# vco.net
KiCad netlist of a schematic drawn in EAGLE
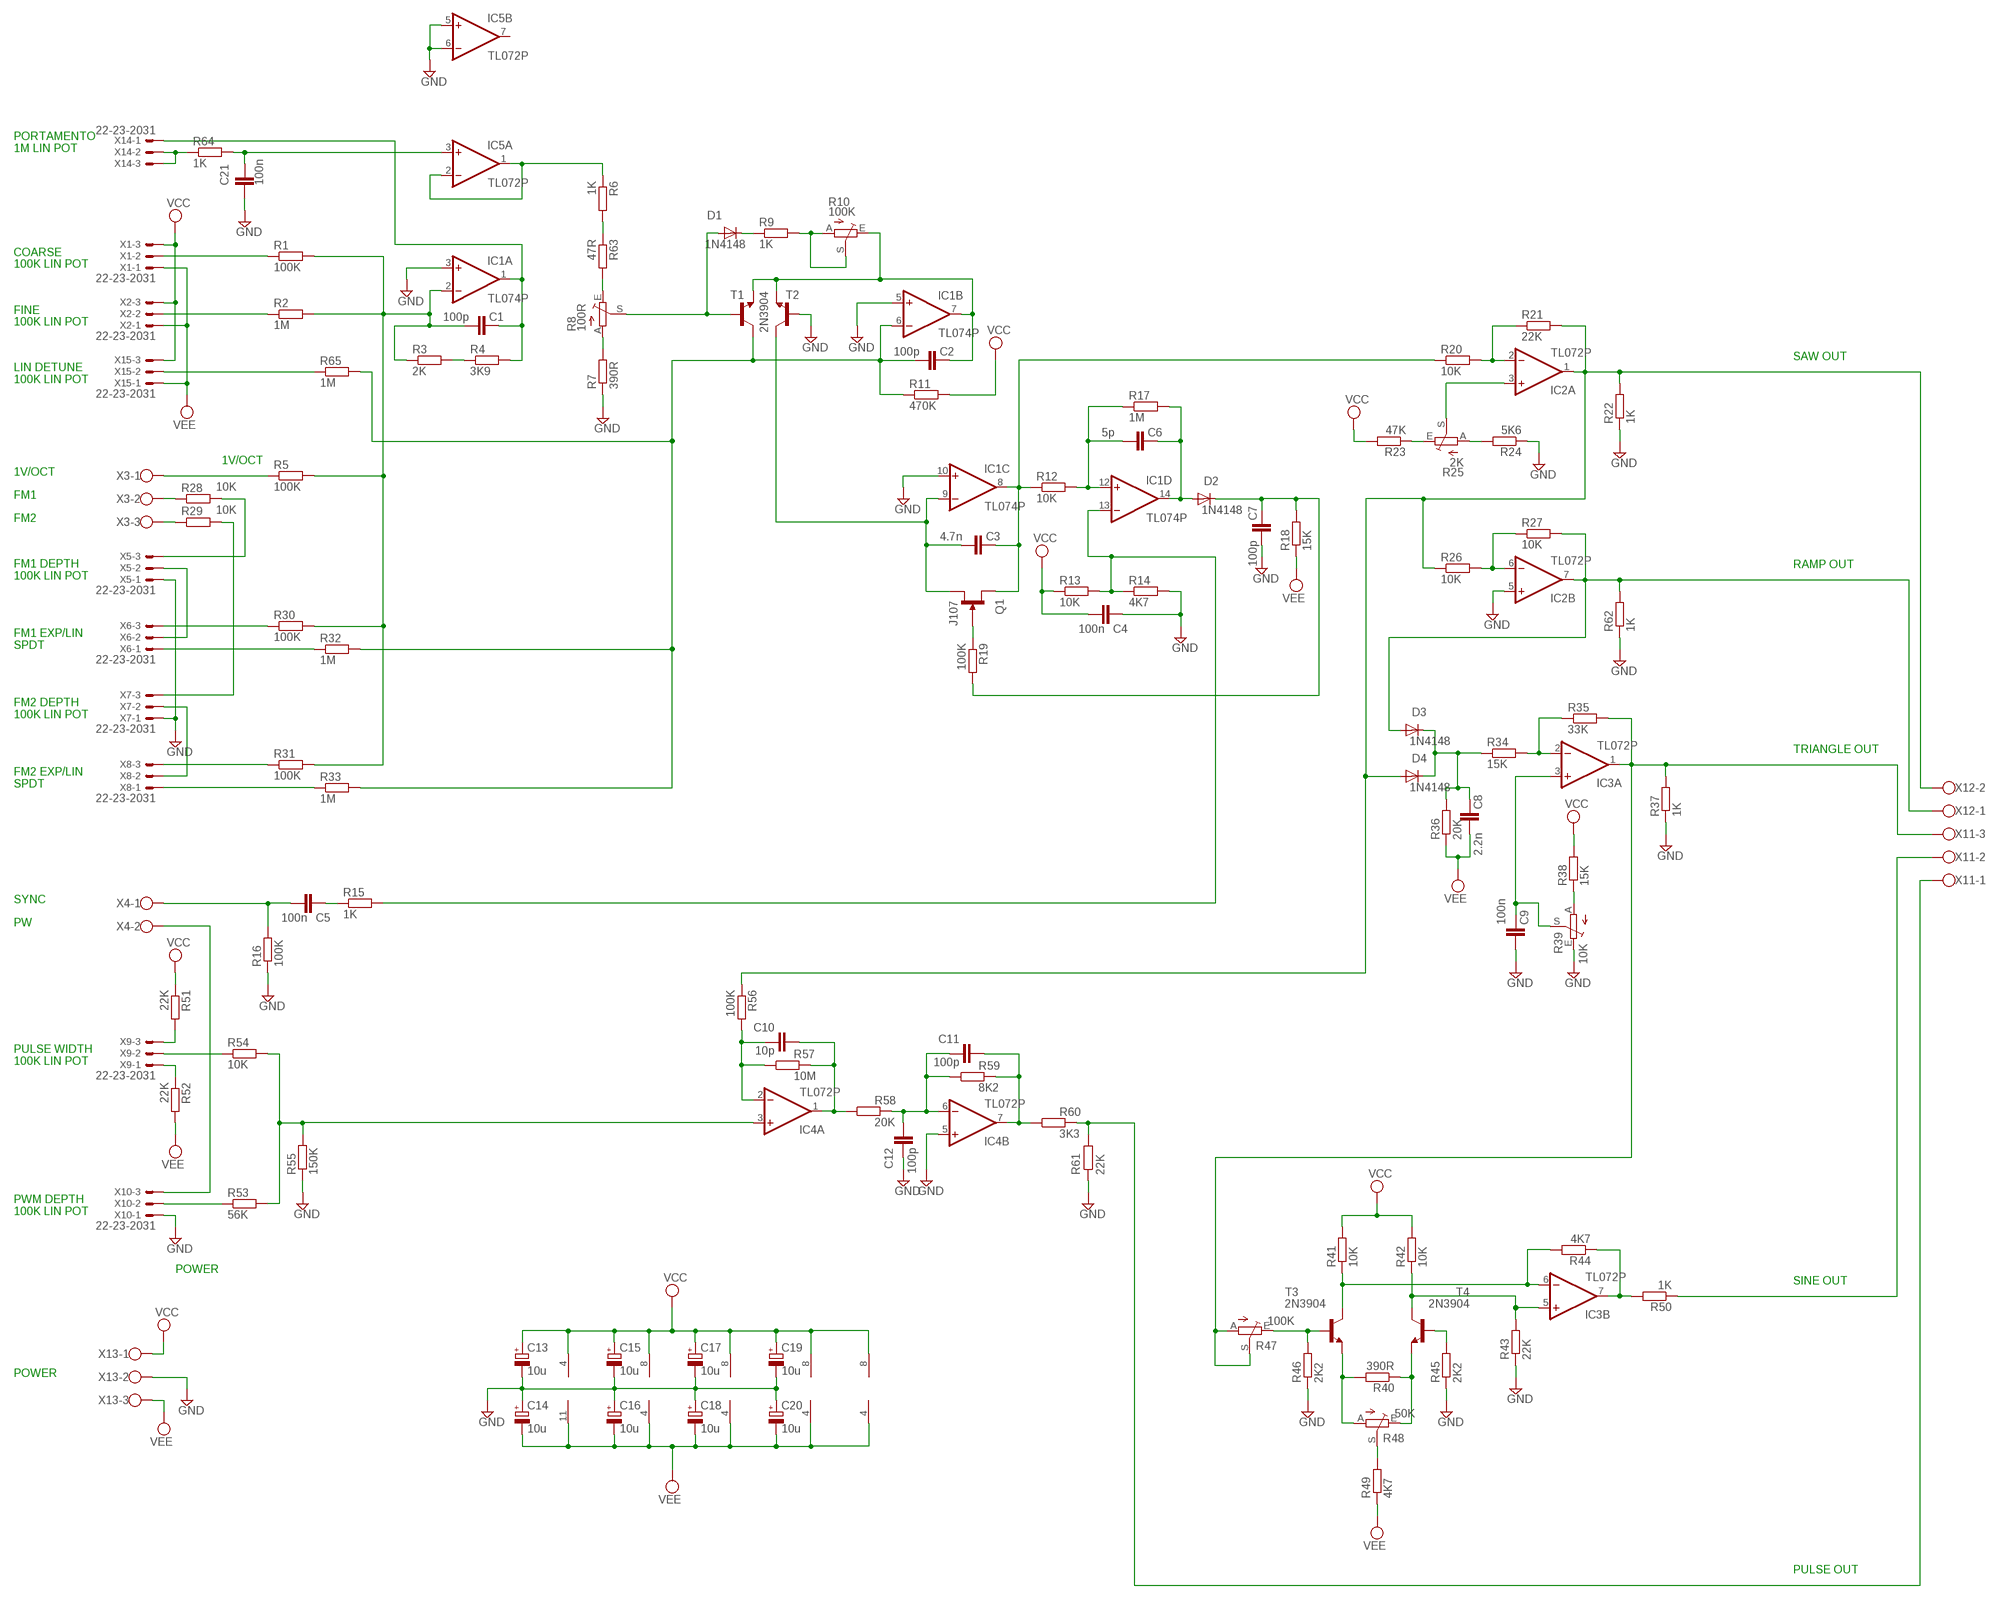
[diagram p0: schematic, sheet 1]

(export (version "E")
  (design (tool "Eeschema 10.0.6"))
  (components
    (comp (ref "C1")
      (value "100p")
      (footprint "eagle-import:C025-024X044")
      (libsource (lib "eagle-import") (part "C-EU025-024X044"))
    )
    (comp (ref "C2")
      (value "100p")
      (footprint "eagle-import:C025-024X044")
      (libsource (lib "eagle-import") (part "C-EU025-024X044"))
    )
    (comp (ref "C3")
      (value "4.7n")
      (footprint "eagle-import:C025-024X044")
      (libsource (lib "eagle-import") (part "C-EU025-024X044"))
    )
    (comp (ref "C4")
      (value "100n")
      (footprint "eagle-import:C025-024X044")
      (libsource (lib "eagle-import") (part "C-EU025-024X044"))
    )
    (comp (ref "C5")
      (value "100n")
      (footprint "eagle-import:C025-024X044")
      (libsource (lib "eagle-import") (part "C-EU025-024X044"))
    )
    (comp (ref "C6")
      (value "5p")
      (footprint "eagle-import:C025-024X044")
      (libsource (lib "eagle-import") (part "C-EU025-024X044"))
    )
    (comp (ref "C7")
      (value "100p")
      (footprint "eagle-import:C025-024X044")
      (libsource (lib "eagle-import") (part "C-EU025-024X044"))
    )
    (comp (ref "C8")
      (value "2.2n")
      (footprint "eagle-import:C025-024X044")
      (libsource (lib "eagle-import") (part "C-EU025-024X044"))
    )
    (comp (ref "C9")
      (value "100n")
      (footprint "eagle-import:C025-024X044")
      (libsource (lib "eagle-import") (part "C-EU025-024X044"))
    )
    (comp (ref "C10")
      (value "10p")
      (footprint "eagle-import:C025-024X044")
      (libsource (lib "eagle-import") (part "C-EU025-024X044"))
    )
    (comp (ref "C11")
      (value "100p")
      (footprint "eagle-import:C025-024X044")
      (libsource (lib "eagle-import") (part "C-EU025-024X044"))
    )
    (comp (ref "C12")
      (value "100p")
      (footprint "eagle-import:C025-024X044")
      (libsource (lib "eagle-import") (part "C-EU025-024X044"))
    )
    (comp (ref "C13")
      (value "10u")
      (footprint "eagle-import:E1,8-4")
      (libsource (lib "eagle-import") (part "CPOL-EUE1.8-4"))
    )
    (comp (ref "C14")
      (value "10u")
      (footprint "eagle-import:E1,8-4")
      (libsource (lib "eagle-import") (part "CPOL-EUE1.8-4"))
    )
    (comp (ref "C15")
      (value "10u")
      (footprint "eagle-import:E1,8-4")
      (libsource (lib "eagle-import") (part "CPOL-EUE1.8-4"))
    )
    (comp (ref "C16")
      (value "10u")
      (footprint "eagle-import:E1,8-4")
      (libsource (lib "eagle-import") (part "CPOL-EUE1.8-4"))
    )
    (comp (ref "C17")
      (value "10u")
      (footprint "eagle-import:E1,8-4")
      (libsource (lib "eagle-import") (part "CPOL-EUE1.8-4"))
    )
    (comp (ref "C18")
      (value "10u")
      (footprint "eagle-import:E1,8-4")
      (libsource (lib "eagle-import") (part "CPOL-EUE1.8-4"))
    )
    (comp (ref "C19")
      (value "10u")
      (footprint "eagle-import:E1,8-4")
      (libsource (lib "eagle-import") (part "CPOL-EUE1.8-4"))
    )
    (comp (ref "C20")
      (value "10u")
      (footprint "eagle-import:E1,8-4")
      (libsource (lib "eagle-import") (part "CPOL-EUE1.8-4"))
    )
    (comp (ref "C21")
      (value "100n")
      (footprint "eagle-import:C025-024X044")
      (libsource (lib "eagle-import") (part "C-EU025-024X044"))
    )
    (comp (ref "D1")
      (value "1N4148")
      (footprint "eagle-import:DO35-7")
      (libsource (lib "eagle-import") (part "1N4148DO35-7"))
    )
    (comp (ref "D2")
      (value "1N4148")
      (footprint "eagle-import:DO35-7")
      (libsource (lib "eagle-import") (part "1N4148DO35-7"))
    )
    (comp (ref "D3")
      (value "1N4148")
      (footprint "eagle-import:DO35-7")
      (libsource (lib "eagle-import") (part "1N4148DO35-7"))
    )
    (comp (ref "D4")
      (value "1N4148")
      (footprint "eagle-import:DO35-7")
      (libsource (lib "eagle-import") (part "1N4148DO35-7"))
    )
    (comp (ref "IC1")
      (value "TL074P")
      (footprint "eagle-import:DIL14")
      (libsource (lib "eagle-import") (part "TL074P"))
    )
    (comp (ref "IC2")
      (value "TL072P")
      (footprint "eagle-import:DIL08")
      (libsource (lib "eagle-import") (part "TL072P"))
    )
    (comp (ref "IC3")
      (value "TL072P")
      (footprint "eagle-import:DIL08")
      (libsource (lib "eagle-import") (part "TL072P"))
    )
    (comp (ref "IC4")
      (value "TL072P")
      (footprint "eagle-import:DIL08")
      (libsource (lib "eagle-import") (part "TL072P"))
    )
    (comp (ref "IC5")
      (value "TL072P")
      (footprint "eagle-import:DIL08")
      (libsource (lib "eagle-import") (part "TL072P"))
    )
    (comp (ref "Q1")
      (value "J107")
      (footprint "eagle-import:TO92R")
      (libsource (lib "eagle-import") (part "J105"))
    )
    (comp (ref "R1")
      (value "100K")
      (footprint "eagle-import:0204_7")
      (libsource (lib "eagle-import") (part "R-EU_0204/7"))
    )
    (comp (ref "R2")
      (value "1M")
      (footprint "eagle-import:0204_7")
      (libsource (lib "eagle-import") (part "R-EU_0204/7"))
    )
    (comp (ref "R3")
      (value "2K")
      (footprint "eagle-import:0309_12")
      (libsource (lib "eagle-import") (part "R-EU_0309/12"))
    )
    (comp (ref "R4")
      (value "3K9")
      (footprint "eagle-import:0204_7")
      (libsource (lib "eagle-import") (part "R-EU_0204/7"))
    )
    (comp (ref "R5")
      (value "100K")
      (footprint "eagle-import:0204_7")
      (libsource (lib "eagle-import") (part "R-EU_0204/7"))
    )
    (comp (ref "R6")
      (value "1K")
      (footprint "eagle-import:0204_7")
      (libsource (lib "eagle-import") (part "R-EU_0204/7"))
    )
    (comp (ref "R7")
      (value "390R")
      (footprint "eagle-import:0204_7")
      (libsource (lib "eagle-import") (part "R-EU_0204/7"))
    )
    (comp (ref "R8")
      (value "100R")
      (footprint "eagle-import:B64Y")
      (libsource (lib "eagle-import") (part "TRIM_EU-B64Y"))
    )
    (comp (ref "R9")
      (value "1K")
      (footprint "eagle-import:0204_7")
      (libsource (lib "eagle-import") (part "R-EU_0204/7"))
    )
    (comp (ref "R10")
      (value "100K")
      (footprint "eagle-import:B64Y")
      (libsource (lib "eagle-import") (part "TRIM_EU-B64Y"))
    )
    (comp (ref "R11")
      (value "470K")
      (footprint "eagle-import:0204_7")
      (libsource (lib "eagle-import") (part "R-EU_0204/7"))
    )
    (comp (ref "R12")
      (value "10K")
      (footprint "eagle-import:0204_7")
      (libsource (lib "eagle-import") (part "R-EU_0204/7"))
    )
    (comp (ref "R13")
      (value "10K")
      (footprint "eagle-import:0204_7")
      (libsource (lib "eagle-import") (part "R-EU_0204/7"))
    )
    (comp (ref "R14")
      (value "4K7")
      (footprint "eagle-import:0204_7")
      (libsource (lib "eagle-import") (part "R-EU_0204/7"))
    )
    (comp (ref "R15")
      (value "1K")
      (footprint "eagle-import:0204_7")
      (libsource (lib "eagle-import") (part "R-EU_0204/7"))
    )
    (comp (ref "R16")
      (value "100K")
      (footprint "eagle-import:0204_7")
      (libsource (lib "eagle-import") (part "R-EU_0204/7"))
    )
    (comp (ref "R17")
      (value "1M")
      (footprint "eagle-import:0204_7")
      (libsource (lib "eagle-import") (part "R-EU_0204/7"))
    )
    (comp (ref "R18")
      (value "15K")
      (footprint "eagle-import:0204_7")
      (libsource (lib "eagle-import") (part "R-EU_0204/7"))
    )
    (comp (ref "R19")
      (value "100K")
      (footprint "eagle-import:0204_7")
      (libsource (lib "eagle-import") (part "R-EU_0204/7"))
    )
    (comp (ref "R20")
      (value "10K")
      (footprint "eagle-import:0204_7")
      (libsource (lib "eagle-import") (part "R-EU_0204/7"))
    )
    (comp (ref "R21")
      (value "22K")
      (footprint "eagle-import:0204_7")
      (libsource (lib "eagle-import") (part "R-EU_0204/7"))
    )
    (comp (ref "R22")
      (value "1K")
      (footprint "eagle-import:0204_7")
      (libsource (lib "eagle-import") (part "R-EU_0204/7"))
    )
    (comp (ref "R23")
      (value "47K")
      (footprint "eagle-import:0204_7")
      (libsource (lib "eagle-import") (part "R-EU_0204/7"))
    )
    (comp (ref "R24")
      (value "5K6")
      (footprint "eagle-import:0204_7")
      (libsource (lib "eagle-import") (part "R-EU_0204/7"))
    )
    (comp (ref "R25")
      (value "2K")
      (footprint "eagle-import:B64Y")
      (libsource (lib "eagle-import") (part "TRIM_EU-B64Y"))
    )
    (comp (ref "R26")
      (value "10K")
      (footprint "eagle-import:0204_7")
      (libsource (lib "eagle-import") (part "R-EU_0204/7"))
    )
    (comp (ref "R27")
      (value "10K")
      (footprint "eagle-import:0204_7")
      (libsource (lib "eagle-import") (part "R-EU_0204/7"))
    )
    (comp (ref "R28")
      (value "10K")
      (footprint "eagle-import:0204_7")
      (libsource (lib "eagle-import") (part "R-EU_0204/7"))
    )
    (comp (ref "R29")
      (value "10K")
      (footprint "eagle-import:0204_7")
      (libsource (lib "eagle-import") (part "R-EU_0204/7"))
    )
    (comp (ref "R30")
      (value "100K")
      (footprint "eagle-import:0204_7")
      (libsource (lib "eagle-import") (part "R-EU_0204/7"))
    )
    (comp (ref "R31")
      (value "100K")
      (footprint "eagle-import:0204_7")
      (libsource (lib "eagle-import") (part "R-EU_0204/7"))
    )
    (comp (ref "R32")
      (value "1M")
      (footprint "eagle-import:0204_7")
      (libsource (lib "eagle-import") (part "R-EU_0204/7"))
    )
    (comp (ref "R33")
      (value "1M")
      (footprint "eagle-import:0204_7")
      (libsource (lib "eagle-import") (part "R-EU_0204/7"))
    )
    (comp (ref "R34")
      (value "15K")
      (footprint "eagle-import:0204_7")
      (libsource (lib "eagle-import") (part "R-EU_0204/7"))
    )
    (comp (ref "R35")
      (value "33K")
      (footprint "eagle-import:0204_7")
      (libsource (lib "eagle-import") (part "R-EU_0204/7"))
    )
    (comp (ref "R36")
      (value "20K")
      (footprint "eagle-import:0204_7")
      (libsource (lib "eagle-import") (part "R-EU_0204/7"))
    )
    (comp (ref "R37")
      (value "1K")
      (footprint "eagle-import:0204_7")
      (libsource (lib "eagle-import") (part "R-EU_0204/7"))
    )
    (comp (ref "R38")
      (value "15K")
      (footprint "eagle-import:0204_7")
      (libsource (lib "eagle-import") (part "R-EU_0204/7"))
    )
    (comp (ref "R39")
      (value "10K")
      (footprint "eagle-import:CA6V")
      (libsource (lib "eagle-import") (part "TRIM_EU-CA6V"))
    )
    (comp (ref "R40")
      (value "390R")
      (footprint "eagle-import:0204_7")
      (libsource (lib "eagle-import") (part "R-EU_0204/7"))
    )
    (comp (ref "R41")
      (value "10K")
      (footprint "eagle-import:0204_7")
      (libsource (lib "eagle-import") (part "R-EU_0204/7"))
    )
    (comp (ref "R42")
      (value "10K")
      (footprint "eagle-import:0204_7")
      (libsource (lib "eagle-import") (part "R-EU_0204/7"))
    )
    (comp (ref "R43")
      (value "22K")
      (footprint "eagle-import:0204_7")
      (libsource (lib "eagle-import") (part "R-EU_0204/7"))
    )
    (comp (ref "R44")
      (value "4K7")
      (footprint "eagle-import:0204_7")
      (libsource (lib "eagle-import") (part "R-EU_0204/7"))
    )
    (comp (ref "R45")
      (value "2K2")
      (footprint "eagle-import:0204_7")
      (libsource (lib "eagle-import") (part "R-EU_0204/7"))
    )
    (comp (ref "R46")
      (value "2K2")
      (footprint "eagle-import:0204_7")
      (libsource (lib "eagle-import") (part "R-EU_0204/7"))
    )
    (comp (ref "R47")
      (value "100K")
      (footprint "eagle-import:CA6V")
      (libsource (lib "eagle-import") (part "TRIM_EU-CA6V"))
    )
    (comp (ref "R48")
      (value "50K")
      (footprint "eagle-import:CA6V")
      (libsource (lib "eagle-import") (part "TRIM_EU-CA6V"))
    )
    (comp (ref "R49")
      (value "4K7")
      (footprint "eagle-import:0204_7")
      (libsource (lib "eagle-import") (part "R-EU_0204/7"))
    )
    (comp (ref "R50")
      (value "1K")
      (footprint "eagle-import:0204_7")
      (libsource (lib "eagle-import") (part "R-EU_0204/7"))
    )
    (comp (ref "R51")
      (value "22K")
      (footprint "eagle-import:0204_7")
      (libsource (lib "eagle-import") (part "R-EU_0204/7"))
    )
    (comp (ref "R52")
      (value "22K")
      (footprint "eagle-import:0204_7")
      (libsource (lib "eagle-import") (part "R-EU_0204/7"))
    )
    (comp (ref "R53")
      (value "56K")
      (footprint "eagle-import:0204_7")
      (libsource (lib "eagle-import") (part "R-EU_0204/7"))
    )
    (comp (ref "R54")
      (value "10K")
      (footprint "eagle-import:0204_7")
      (libsource (lib "eagle-import") (part "R-EU_0204/7"))
    )
    (comp (ref "R55")
      (value "150K")
      (footprint "eagle-import:0204_7")
      (libsource (lib "eagle-import") (part "R-EU_0204/7"))
    )
    (comp (ref "R56")
      (value "100K")
      (footprint "eagle-import:0204_7")
      (libsource (lib "eagle-import") (part "R-EU_0204/7"))
    )
    (comp (ref "R57")
      (value "10M")
      (footprint "eagle-import:0204_7")
      (libsource (lib "eagle-import") (part "R-EU_0204/7"))
    )
    (comp (ref "R58")
      (value "20K")
      (footprint "eagle-import:0204_7")
      (libsource (lib "eagle-import") (part "R-EU_0204/7"))
    )
    (comp (ref "R59")
      (value "8K2")
      (footprint "eagle-import:0204_7")
      (libsource (lib "eagle-import") (part "R-EU_0204/7"))
    )
    (comp (ref "R60")
      (value "3K3")
      (footprint "eagle-import:0204_7")
      (libsource (lib "eagle-import") (part "R-EU_0204/7"))
    )
    (comp (ref "R61")
      (value "22K")
      (footprint "eagle-import:0204_7")
      (libsource (lib "eagle-import") (part "R-EU_0204/7"))
    )
    (comp (ref "R62")
      (value "1K")
      (footprint "eagle-import:0204_7")
      (libsource (lib "eagle-import") (part "R-EU_0204/7"))
    )
    (comp (ref "R63")
      (value "47R")
      (footprint "eagle-import:0204_7")
      (libsource (lib "eagle-import") (part "R-EU_0204/7"))
    )
    (comp (ref "R64")
      (value "1K")
      (footprint "eagle-import:0204_7")
      (libsource (lib "eagle-import") (part "R-EU_0204/7"))
    )
    (comp (ref "R65")
      (value "1M")
      (footprint "eagle-import:0204_7")
      (libsource (lib "eagle-import") (part "R-EU_0204/7"))
    )
    (comp (ref "T1")
      (value "2N3904")
      (footprint "eagle-import:TO92")
      (libsource (lib "eagle-import") (part "2N3904"))
    )
    (comp (ref "T2")
      (value "2N3904")
      (footprint "eagle-import:TO92")
      (libsource (lib "eagle-import") (part "2N3904"))
    )
    (comp (ref "T3")
      (value "2N3904")
      (footprint "eagle-import:TO92")
      (libsource (lib "eagle-import") (part "2N3904"))
    )
    (comp (ref "T4")
      (value "2N3904")
      (footprint "eagle-import:TO92")
      (libsource (lib "eagle-import") (part "2N3904"))
    )
    (comp (ref "X1")
      (value "22-23-2031")
      (footprint "eagle-import:22-23-2031")
      (fields (field (name "MF") "MOLEX"))
      (libsource (lib "eagle-import") (part "22-23-2031"))
    )
    (comp (ref "X2")
      (value "22-23-2031")
      (footprint "eagle-import:22-23-2031")
      (fields (field (name "MF") "MOLEX"))
      (libsource (lib "eagle-import") (part "22-23-2031"))
    )
    (comp (ref "X3")
      (value "W237-103")
      (footprint "eagle-import:W237-103")
      (fields (field (name "MPN") "237-103"))
      (libsource (lib "eagle-import") (part "W237-103"))
    )
    (comp (ref "X4")
      (value "W237-102")
      (footprint "eagle-import:W237-102")
      (fields (field (name "MPN") "237-102"))
      (libsource (lib "eagle-import") (part "W237-102"))
    )
    (comp (ref "X5")
      (value "22-23-2031")
      (footprint "eagle-import:22-23-2031")
      (fields (field (name "MF") "MOLEX"))
      (libsource (lib "eagle-import") (part "22-23-2031"))
    )
    (comp (ref "X6")
      (value "22-23-2031")
      (footprint "eagle-import:22-23-2031")
      (fields (field (name "MF") "MOLEX"))
      (libsource (lib "eagle-import") (part "22-23-2031"))
    )
    (comp (ref "X7")
      (value "22-23-2031")
      (footprint "eagle-import:22-23-2031")
      (fields (field (name "MF") "MOLEX"))
      (libsource (lib "eagle-import") (part "22-23-2031"))
    )
    (comp (ref "X8")
      (value "22-23-2031")
      (footprint "eagle-import:22-23-2031")
      (fields (field (name "MF") "MOLEX"))
      (libsource (lib "eagle-import") (part "22-23-2031"))
    )
    (comp (ref "X9")
      (value "22-23-2031")
      (footprint "eagle-import:22-23-2031")
      (fields (field (name "MF") "MOLEX"))
      (libsource (lib "eagle-import") (part "22-23-2031"))
    )
    (comp (ref "X10")
      (value "22-23-2031")
      (footprint "eagle-import:22-23-2031")
      (fields (field (name "MF") "MOLEX"))
      (libsource (lib "eagle-import") (part "22-23-2031"))
    )
    (comp (ref "X11")
      (value "W237-103")
      (footprint "eagle-import:W237-103")
      (fields (field (name "MPN") "237-103"))
      (libsource (lib "eagle-import") (part "W237-103"))
    )
    (comp (ref "X12")
      (value "W237-102")
      (footprint "eagle-import:W237-102")
      (fields (field (name "MPN") "237-102"))
      (libsource (lib "eagle-import") (part "W237-102"))
    )
    (comp (ref "X13")
      (value "W237-103")
      (footprint "eagle-import:W237-103")
      (fields (field (name "MPN") "237-103"))
      (libsource (lib "eagle-import") (part "W237-103"))
    )
    (comp (ref "X14")
      (value "22-23-2031")
      (footprint "eagle-import:22-23-2031")
      (fields (field (name "MF") "MOLEX"))
      (libsource (lib "eagle-import") (part "22-23-2031"))
    )
    (comp (ref "X15")
      (value "22-23-2031")
      (footprint "eagle-import:22-23-2031")
      (fields (field (name "MF") "MOLEX"))
      (libsource (lib "eagle-import") (part "22-23-2031"))
    )
  )
  (nets
    (net (code "1") (name "GND") (class "Default")
      (node (ref "C12") (pin "1") (pinfunction "1_1") (pintype "passive"))
      (node (ref "C13") (pin "-") (pinfunction "-_-") (pintype "passive"))
      (node (ref "C14") (pin "+") (pinfunction "+_+") (pintype "passive"))
      (node (ref "C15") (pin "-") (pinfunction "-_-") (pintype "passive"))
      (node (ref "C16") (pin "+") (pinfunction "+_+") (pintype "passive"))
      (node (ref "C17") (pin "-") (pinfunction "-_-") (pintype "passive"))
      (node (ref "C18") (pin "+") (pinfunction "+_+") (pintype "passive"))
      (node (ref "C19") (pin "-") (pinfunction "-_-") (pintype "passive"))
      (node (ref "C20") (pin "+") (pinfunction "+_+") (pintype "passive"))
      (node (ref "C21") (pin "2") (pinfunction "2_2") (pintype "passive"))
      (node (ref "C4") (pin "1") (pinfunction "1_1") (pintype "passive"))
      (node (ref "C7") (pin "2") (pinfunction "2_2") (pintype "passive"))
      (node (ref "C9") (pin "2") (pinfunction "2_2") (pintype "passive"))
      (node (ref "IC1") (pin "10") (pinfunction "+IN_10") (pintype "input"))
      (node (ref "IC1") (pin "3") (pinfunction "+IN_3") (pintype "input"))
      (node (ref "IC1") (pin "5") (pinfunction "+IN_5") (pintype "input"))
      (node (ref "IC2") (pin "5") (pinfunction "+IN_5") (pintype "input"))
      (node (ref "IC4") (pin "5") (pinfunction "+IN_5") (pintype "input"))
      (node (ref "IC5") (pin "5") (pinfunction "+IN_5") (pintype "input"))
      (node (ref "IC5") (pin "6") (pinfunction "-IN_6") (pintype "input"))
      (node (ref "R14") (pin "2") (pinfunction "2_2") (pintype "passive"))
      (node (ref "R16") (pin "1") (pinfunction "1_1") (pintype "passive"))
      (node (ref "R22") (pin "1") (pinfunction "1_1") (pintype "passive"))
      (node (ref "R24") (pin "1") (pinfunction "1_1") (pintype "passive"))
      (node (ref "R37") (pin "1") (pinfunction "1_1") (pintype "passive"))
      (node (ref "R39") (pin "E") (pinfunction "E_E") (pintype "passive"))
      (node (ref "R43") (pin "1") (pinfunction "1_1") (pintype "passive"))
      (node (ref "R45") (pin "1") (pinfunction "1_1") (pintype "passive"))
      (node (ref "R46") (pin "1") (pinfunction "1_1") (pintype "passive"))
      (node (ref "R55") (pin "1") (pinfunction "1_1") (pintype "passive"))
      (node (ref "R61") (pin "1") (pinfunction "1_1") (pintype "passive"))
      (node (ref "R62") (pin "1") (pinfunction "1_1") (pintype "passive"))
      (node (ref "R7") (pin "1") (pinfunction "1_1") (pintype "passive"))
      (node (ref "T2") (pin "2") (pinfunction "B_2") (pintype "passive"))
      (node (ref "X10") (pin "1") (pinfunction "S_1") (pintype "passive"))
      (node (ref "X13") (pin "2") (pinfunction "KL_2") (pintype "passive"))
      (node (ref "X5") (pin "1") (pinfunction "S_1") (pintype "passive"))
      (node (ref "X7") (pin "1") (pinfunction "S_1") (pintype "passive"))
    )
    (net (code "2") (name "Net-(C5-Pad1)") (class "Default")
      (node (ref "C5") (pin "1") (pinfunction "1_1") (pintype "passive"))
      (node (ref "R15") (pin "1") (pinfunction "1_1") (pintype "passive"))
    )
    (net (code "3") (name "Net-(C7-Pad1)") (class "Default")
      (node (ref "C7") (pin "1") (pinfunction "1_1") (pintype "passive"))
      (node (ref "D2") (pin "C") (pinfunction "C_C") (pintype "passive"))
      (node (ref "R18") (pin "2") (pinfunction "2_2") (pintype "passive"))
      (node (ref "R19") (pin "2") (pinfunction "2_2") (pintype "passive"))
    )
    (net (code "4") (name "Net-(C8-Pad1)") (class "Default")
      (node (ref "C8") (pin "1") (pinfunction "1_1") (pintype "passive"))
      (node (ref "D3") (pin "C") (pinfunction "C_C") (pintype "passive"))
      (node (ref "D4") (pin "C") (pinfunction "C_C") (pintype "passive"))
      (node (ref "R34") (pin "1") (pinfunction "1_1") (pintype "passive"))
      (node (ref "R36") (pin "2") (pinfunction "2_2") (pintype "passive"))
    )
    (net (code "5") (name "Net-(D1-PadC)") (class "Default")
      (node (ref "D1") (pin "C") (pinfunction "C_C") (pintype "passive"))
      (node (ref "R9") (pin "1") (pinfunction "1_1") (pintype "passive"))
    )
    (net (code "6") (name "Net-(IC1A--IN)") (class "Default")
      (node (ref "C1") (pin "2") (pinfunction "2_2") (pintype "passive"))
      (node (ref "IC1") (pin "2") (pinfunction "-IN_2") (pintype "input"))
      (node (ref "R1") (pin "2") (pinfunction "2_2") (pintype "passive"))
      (node (ref "R2") (pin "2") (pinfunction "2_2") (pintype "passive"))
      (node (ref "R3") (pin "1") (pinfunction "1_1") (pintype "passive"))
      (node (ref "R30") (pin "2") (pinfunction "2_2") (pintype "passive"))
      (node (ref "R31") (pin "2") (pinfunction "2_2") (pintype "passive"))
      (node (ref "R5") (pin "2") (pinfunction "2_2") (pintype "passive"))
    )
    (net (code "7") (name "Net-(IC1A-OUT)") (class "Default")
      (node (ref "C1") (pin "1") (pinfunction "1_1") (pintype "passive"))
      (node (ref "IC1") (pin "1") (pinfunction "OUT_1") (pintype "output"))
      (node (ref "R4") (pin "2") (pinfunction "2_2") (pintype "passive"))
      (node (ref "X14") (pin "1") (pinfunction "S_1") (pintype "passive"))
    )
    (net (code "8") (name "Net-(IC1B--IN)") (class "Default")
      (node (ref "C2") (pin "2") (pinfunction "2_2") (pintype "passive"))
      (node (ref "IC1") (pin "6") (pinfunction "-IN_6") (pintype "input"))
      (node (ref "R11") (pin "1") (pinfunction "1_1") (pintype "passive"))
      (node (ref "R32") (pin "2") (pinfunction "2_2") (pintype "passive"))
      (node (ref "R33") (pin "2") (pinfunction "2_2") (pintype "passive"))
      (node (ref "R65") (pin "2") (pinfunction "2_2") (pintype "passive"))
      (node (ref "T1") (pin "1") (pinfunction "C_1") (pintype "passive"))
    )
    (net (code "9") (name "Net-(IC1B-OUT)") (class "Default")
      (node (ref "C2") (pin "1") (pinfunction "1_1") (pintype "passive"))
      (node (ref "IC1") (pin "7") (pinfunction "OUT_7") (pintype "output"))
      (node (ref "R10") (pin "E") (pinfunction "E_E") (pintype "passive"))
      (node (ref "T1") (pin "3") (pinfunction "E_3") (pintype "passive"))
      (node (ref "T2") (pin "3") (pinfunction "E_3") (pintype "passive"))
    )
    (net (code "10") (name "Net-(IC1C--IN)") (class "Default")
      (node (ref "C3") (pin "2") (pinfunction "2_2") (pintype "passive"))
      (node (ref "IC1") (pin "9") (pinfunction "-IN_9") (pintype "input"))
      (node (ref "Q1") (pin "S") (pinfunction "S_S") (pintype "passive"))
      (node (ref "T2") (pin "1") (pinfunction "C_1") (pintype "passive"))
    )
    (net (code "11") (name "Net-(IC1C-OUT)") (class "Default")
      (node (ref "C3") (pin "1") (pinfunction "1_1") (pintype "passive"))
      (node (ref "IC1") (pin "8") (pinfunction "OUT_8") (pintype "output"))
      (node (ref "Q1") (pin "D") (pinfunction "D_D") (pintype "passive"))
      (node (ref "R12") (pin "1") (pinfunction "1_1") (pintype "passive"))
      (node (ref "R20") (pin "1") (pinfunction "1_1") (pintype "passive"))
    )
    (net (code "12") (name "Net-(IC1D-+IN)") (class "Default")
      (node (ref "C6") (pin "2") (pinfunction "2_2") (pintype "passive"))
      (node (ref "IC1") (pin "12") (pinfunction "+IN_12") (pintype "input"))
      (node (ref "R12") (pin "2") (pinfunction "2_2") (pintype "passive"))
      (node (ref "R17") (pin "1") (pinfunction "1_1") (pintype "passive"))
    )
    (net (code "13") (name "Net-(IC1D--IN)") (class "Default")
      (node (ref "IC1") (pin "13") (pinfunction "-IN_13") (pintype "input"))
      (node (ref "R13") (pin "2") (pinfunction "2_2") (pintype "passive"))
      (node (ref "R14") (pin "1") (pinfunction "1_1") (pintype "passive"))
      (node (ref "R15") (pin "2") (pinfunction "2_2") (pintype "passive"))
    )
    (net (code "14") (name "Net-(IC1D-OUT)") (class "Default")
      (node (ref "C6") (pin "1") (pinfunction "1_1") (pintype "passive"))
      (node (ref "D2") (pin "A") (pinfunction "A_A") (pintype "passive"))
      (node (ref "IC1") (pin "14") (pinfunction "OUT_14") (pintype "output"))
      (node (ref "R17") (pin "2") (pinfunction "2_2") (pintype "passive"))
    )
    (net (code "15") (name "Net-(IC2A-+IN)") (class "Default")
      (node (ref "IC2") (pin "3") (pinfunction "+IN_3") (pintype "input"))
      (node (ref "R25") (pin "S") (pinfunction "S_S") (pintype "passive"))
    )
    (net (code "16") (name "Net-(IC2A--IN)") (class "Default")
      (node (ref "IC2") (pin "2") (pinfunction "-IN_2") (pintype "input"))
      (node (ref "R20") (pin "2") (pinfunction "2_2") (pintype "passive"))
      (node (ref "R21") (pin "1") (pinfunction "1_1") (pintype "passive"))
    )
    (net (code "17") (name "Net-(IC2A-OUT)") (class "Default")
      (node (ref "D4") (pin "A") (pinfunction "A_A") (pintype "passive"))
      (node (ref "IC2") (pin "1") (pinfunction "OUT_1") (pintype "output"))
      (node (ref "R21") (pin "2") (pinfunction "2_2") (pintype "passive"))
      (node (ref "R22") (pin "2") (pinfunction "2_2") (pintype "passive"))
      (node (ref "R26") (pin "1") (pinfunction "1_1") (pintype "passive"))
      (node (ref "R56") (pin "1") (pinfunction "1_1") (pintype "passive"))
      (node (ref "X12") (pin "2") (pinfunction "KL_2") (pintype "passive"))
    )
    (net (code "18") (name "Net-(IC2B--IN)") (class "Default")
      (node (ref "IC2") (pin "6") (pinfunction "-IN_6") (pintype "input"))
      (node (ref "R26") (pin "2") (pinfunction "2_2") (pintype "passive"))
      (node (ref "R27") (pin "1") (pinfunction "1_1") (pintype "passive"))
    )
    (net (code "19") (name "Net-(IC2B-OUT)") (class "Default")
      (node (ref "D3") (pin "A") (pinfunction "A_A") (pintype "passive"))
      (node (ref "IC2") (pin "7") (pinfunction "OUT_7") (pintype "output"))
      (node (ref "R27") (pin "2") (pinfunction "2_2") (pintype "passive"))
      (node (ref "R62") (pin "2") (pinfunction "2_2") (pintype "passive"))
      (node (ref "X12") (pin "1") (pinfunction "KL_1") (pintype "passive"))
    )
    (net (code "20") (name "Net-(IC3A-+IN)") (class "Default")
      (node (ref "C9") (pin "1") (pinfunction "1_1") (pintype "passive"))
      (node (ref "IC3") (pin "3") (pinfunction "+IN_3") (pintype "input"))
      (node (ref "R39") (pin "S") (pinfunction "S_S") (pintype "passive"))
    )
    (net (code "21") (name "Net-(IC3A--IN)") (class "Default")
      (node (ref "IC3") (pin "2") (pinfunction "-IN_2") (pintype "input"))
      (node (ref "R34") (pin "2") (pinfunction "2_2") (pintype "passive"))
      (node (ref "R35") (pin "1") (pinfunction "1_1") (pintype "passive"))
    )
    (net (code "22") (name "Net-(IC3A-OUT)") (class "Default")
      (node (ref "IC3") (pin "1") (pinfunction "OUT_1") (pintype "output"))
      (node (ref "R35") (pin "2") (pinfunction "2_2") (pintype "passive"))
      (node (ref "R37") (pin "2") (pinfunction "2_2") (pintype "passive"))
      (node (ref "R47") (pin "A") (pinfunction "A_A") (pintype "passive"))
      (node (ref "R47") (pin "S") (pinfunction "S_S") (pintype "passive"))
      (node (ref "X11") (pin "3") (pinfunction "KL_3") (pintype "passive"))
    )
    (net (code "23") (name "Net-(IC3B-+IN)") (class "Default")
      (node (ref "IC3") (pin "5") (pinfunction "+IN_5") (pintype "input"))
      (node (ref "R42") (pin "1") (pinfunction "1_1") (pintype "passive"))
      (node (ref "R43") (pin "2") (pinfunction "2_2") (pintype "passive"))
      (node (ref "T4") (pin "1") (pinfunction "C_1") (pintype "passive"))
    )
    (net (code "24") (name "Net-(IC3B--IN)") (class "Default")
      (node (ref "IC3") (pin "6") (pinfunction "-IN_6") (pintype "input"))
      (node (ref "R41") (pin "1") (pinfunction "1_1") (pintype "passive"))
      (node (ref "R44") (pin "2") (pinfunction "2_2") (pintype "passive"))
      (node (ref "T3") (pin "1") (pinfunction "C_1") (pintype "passive"))
    )
    (net (code "25") (name "Net-(IC3B-OUT)") (class "Default")
      (node (ref "IC3") (pin "7") (pinfunction "OUT_7") (pintype "output"))
      (node (ref "R44") (pin "1") (pinfunction "1_1") (pintype "passive"))
      (node (ref "R50") (pin "2") (pinfunction "2_2") (pintype "passive"))
    )
    (net (code "26") (name "Net-(IC4A-+IN)") (class "Default")
      (node (ref "IC4") (pin "3") (pinfunction "+IN_3") (pintype "input"))
      (node (ref "R53") (pin "2") (pinfunction "2_2") (pintype "passive"))
      (node (ref "R54") (pin "2") (pinfunction "2_2") (pintype "passive"))
      (node (ref "R55") (pin "2") (pinfunction "2_2") (pintype "passive"))
    )
    (net (code "27") (name "Net-(IC4A--IN)") (class "Default")
      (node (ref "C10") (pin "1") (pinfunction "1_1") (pintype "passive"))
      (node (ref "IC4") (pin "2") (pinfunction "-IN_2") (pintype "input"))
      (node (ref "R56") (pin "2") (pinfunction "2_2") (pintype "passive"))
      (node (ref "R57") (pin "1") (pinfunction "1_1") (pintype "passive"))
    )
    (net (code "28") (name "Net-(IC4A-OUT)") (class "Default")
      (node (ref "C10") (pin "2") (pinfunction "2_2") (pintype "passive"))
      (node (ref "IC4") (pin "1") (pinfunction "OUT_1") (pintype "output"))
      (node (ref "R57") (pin "2") (pinfunction "2_2") (pintype "passive"))
      (node (ref "R58") (pin "1") (pinfunction "1_1") (pintype "passive"))
    )
    (net (code "29") (name "Net-(IC4B--IN)") (class "Default")
      (node (ref "C11") (pin "1") (pinfunction "1_1") (pintype "passive"))
      (node (ref "C12") (pin "2") (pinfunction "2_2") (pintype "passive"))
      (node (ref "IC4") (pin "6") (pinfunction "-IN_6") (pintype "input"))
      (node (ref "R58") (pin "2") (pinfunction "2_2") (pintype "passive"))
      (node (ref "R59") (pin "1") (pinfunction "1_1") (pintype "passive"))
    )
    (net (code "30") (name "Net-(IC4B-OUT)") (class "Default")
      (node (ref "C11") (pin "2") (pinfunction "2_2") (pintype "passive"))
      (node (ref "IC4") (pin "7") (pinfunction "OUT_7") (pintype "output"))
      (node (ref "R59") (pin "2") (pinfunction "2_2") (pintype "passive"))
      (node (ref "R60") (pin "1") (pinfunction "1_1") (pintype "passive"))
    )
    (net (code "31") (name "Net-(IC5A-+IN)") (class "Default")
      (node (ref "C21") (pin "1") (pinfunction "1_1") (pintype "passive"))
      (node (ref "IC5") (pin "3") (pinfunction "+IN_3") (pintype "input"))
      (node (ref "R64") (pin "2") (pinfunction "2_2") (pintype "passive"))
    )
    (net (code "32") (name "Net-(IC5A--IN)") (class "Default")
      (node (ref "IC5") (pin "1") (pinfunction "OUT_1") (pintype "output"))
      (node (ref "IC5") (pin "2") (pinfunction "-IN_2") (pintype "input"))
      (node (ref "R6") (pin "1") (pinfunction "1_1") (pintype "passive"))
    )
    (net (code "33") (name "Net-(Q1-PadG)") (class "Default")
      (node (ref "Q1") (pin "G") (pinfunction "G_G") (pintype "passive"))
      (node (ref "R19") (pin "1") (pinfunction "1_1") (pintype "passive"))
    )
    (net (code "34") (name "Net-(R3-Pad2)") (class "Default")
      (node (ref "R3") (pin "2") (pinfunction "2_2") (pintype "passive"))
      (node (ref "R4") (pin "1") (pinfunction "1_1") (pintype "passive"))
    )
    (net (code "35") (name "Net-(R6-Pad2)") (class "Default")
      (node (ref "R6") (pin "2") (pinfunction "2_2") (pintype "passive"))
      (node (ref "R63") (pin "1") (pinfunction "1_1") (pintype "passive"))
    )
    (net (code "36") (name "Net-(R7-Pad2)") (class "Default")
      (node (ref "R7") (pin "2") (pinfunction "2_2") (pintype "passive"))
      (node (ref "R8") (pin "A") (pinfunction "A_A") (pintype "passive"))
    )
    (net (code "37") (name "Net-(R10-PadA)") (class "Default")
      (node (ref "R10") (pin "A") (pinfunction "A_A") (pintype "passive"))
      (node (ref "R10") (pin "S") (pinfunction "S_S") (pintype "passive"))
      (node (ref "R9") (pin "2") (pinfunction "2_2") (pintype "passive"))
    )
    (net (code "38") (name "Net-(R23-Pad1)") (class "Default")
      (node (ref "R23") (pin "1") (pinfunction "1_1") (pintype "passive"))
      (node (ref "R25") (pin "E") (pinfunction "E_E") (pintype "passive"))
    )
    (net (code "39") (name "Net-(R24-Pad2)") (class "Default")
      (node (ref "R24") (pin "2") (pinfunction "2_2") (pintype "passive"))
      (node (ref "R25") (pin "A") (pinfunction "A_A") (pintype "passive"))
    )
    (net (code "40") (name "Net-(R38-Pad1)") (class "Default")
      (node (ref "R38") (pin "1") (pinfunction "1_1") (pintype "passive"))
      (node (ref "R39") (pin "A") (pinfunction "A_A") (pintype "passive"))
    )
    (net (code "41") (name "Net-(R48-PadS)") (class "Default")
      (node (ref "R48") (pin "S") (pinfunction "S_S") (pintype "passive"))
      (node (ref "R49") (pin "2") (pinfunction "2_2") (pintype "passive"))
    )
    (net (code "42") (name "Net-(R63-Pad2)") (class "Default")
      (node (ref "R63") (pin "2") (pinfunction "2_2") (pintype "passive"))
      (node (ref "R8") (pin "E") (pinfunction "E_E") (pintype "passive"))
    )
    (net (code "43") (name "Net-(T1-B)") (class "Default")
      (node (ref "D1") (pin "A") (pinfunction "A_A") (pintype "passive"))
      (node (ref "R8") (pin "S") (pinfunction "S_S") (pintype "passive"))
      (node (ref "T1") (pin "2") (pinfunction "B_2") (pintype "passive"))
    )
    (net (code "44") (name "Net-(T3-B)") (class "Default")
      (node (ref "R46") (pin "2") (pinfunction "2_2") (pintype "passive"))
      (node (ref "R47") (pin "E") (pinfunction "E_E") (pintype "passive"))
      (node (ref "T3") (pin "2") (pinfunction "B_2") (pintype "passive"))
    )
    (net (code "45") (name "Net-(T3-E)") (class "Default")
      (node (ref "R40") (pin "2") (pinfunction "2_2") (pintype "passive"))
      (node (ref "R48") (pin "A") (pinfunction "A_A") (pintype "passive"))
      (node (ref "T3") (pin "3") (pinfunction "E_3") (pintype "passive"))
    )
    (net (code "46") (name "Net-(T4-B)") (class "Default")
      (node (ref "R45") (pin "2") (pinfunction "2_2") (pintype "passive"))
      (node (ref "T4") (pin "2") (pinfunction "B_2") (pintype "passive"))
    )
    (net (code "47") (name "Net-(T4-E)") (class "Default")
      (node (ref "R40") (pin "1") (pinfunction "1_1") (pintype "passive"))
      (node (ref "R48") (pin "E") (pinfunction "E_E") (pintype "passive"))
      (node (ref "T4") (pin "3") (pinfunction "E_3") (pintype "passive"))
    )
    (net (code "48") (name "Net-(X1B-S)") (class "Default")
      (node (ref "R1") (pin "1") (pinfunction "1_1") (pintype "passive"))
      (node (ref "X1") (pin "2") (pinfunction "S_2") (pintype "passive"))
    )
    (net (code "49") (name "Net-(X2B-S)") (class "Default")
      (node (ref "R2") (pin "1") (pinfunction "1_1") (pintype "passive"))
      (node (ref "X2") (pin "2") (pinfunction "S_2") (pintype "passive"))
    )
    (net (code "50") (name "Net-(X3A-KL)") (class "Default")
      (node (ref "R5") (pin "1") (pinfunction "1_1") (pintype "passive"))
      (node (ref "X3") (pin "1") (pinfunction "KL_1") (pintype "passive"))
    )
    (net (code "51") (name "Net-(X3B-KL)") (class "Default")
      (node (ref "R28") (pin "1") (pinfunction "1_1") (pintype "passive"))
      (node (ref "X3") (pin "2") (pinfunction "KL_2") (pintype "passive"))
    )
    (net (code "52") (name "Net-(X3C-KL)") (class "Default")
      (node (ref "R29") (pin "1") (pinfunction "1_1") (pintype "passive"))
      (node (ref "X3") (pin "3") (pinfunction "KL_3") (pintype "passive"))
    )
    (net (code "53") (name "Net-(X4A-KL)") (class "Default")
      (node (ref "C5") (pin "2") (pinfunction "2_2") (pintype "passive"))
      (node (ref "R16") (pin "2") (pinfunction "2_2") (pintype "passive"))
      (node (ref "X4") (pin "1") (pinfunction "KL_1") (pintype "passive"))
    )
    (net (code "54") (name "Net-(X5B-S)") (class "Default")
      (node (ref "X5") (pin "2") (pinfunction "S_2") (pintype "passive"))
      (node (ref "X6") (pin "2") (pinfunction "S_2") (pintype "passive"))
    )
    (net (code "55") (name "Net-(X5C-S)") (class "Default")
      (node (ref "R28") (pin "2") (pinfunction "2_2") (pintype "passive"))
      (node (ref "X5") (pin "3") (pinfunction "S_3") (pintype "passive"))
    )
    (net (code "56") (name "Net-(X6A-S)") (class "Default")
      (node (ref "R32") (pin "1") (pinfunction "1_1") (pintype "passive"))
      (node (ref "X6") (pin "1") (pinfunction "S_1") (pintype "passive"))
    )
    (net (code "57") (name "Net-(X6C-S)") (class "Default")
      (node (ref "R30") (pin "1") (pinfunction "1_1") (pintype "passive"))
      (node (ref "X6") (pin "3") (pinfunction "S_3") (pintype "passive"))
    )
    (net (code "58") (name "Net-(X7B-S)") (class "Default")
      (node (ref "X7") (pin "2") (pinfunction "S_2") (pintype "passive"))
      (node (ref "X8") (pin "2") (pinfunction "S_2") (pintype "passive"))
    )
    (net (code "59") (name "Net-(X7C-S)") (class "Default")
      (node (ref "R29") (pin "2") (pinfunction "2_2") (pintype "passive"))
      (node (ref "X7") (pin "3") (pinfunction "S_3") (pintype "passive"))
    )
    (net (code "60") (name "Net-(X8A-S)") (class "Default")
      (node (ref "R33") (pin "1") (pinfunction "1_1") (pintype "passive"))
      (node (ref "X8") (pin "1") (pinfunction "S_1") (pintype "passive"))
    )
    (net (code "61") (name "Net-(X8C-S)") (class "Default")
      (node (ref "R31") (pin "1") (pinfunction "1_1") (pintype "passive"))
      (node (ref "X8") (pin "3") (pinfunction "S_3") (pintype "passive"))
    )
    (net (code "62") (name "Net-(X9A-S)") (class "Default")
      (node (ref "R52") (pin "1") (pinfunction "1_1") (pintype "passive"))
      (node (ref "X9") (pin "1") (pinfunction "S_1") (pintype "passive"))
    )
    (net (code "63") (name "Net-(X9B-S)") (class "Default")
      (node (ref "R54") (pin "1") (pinfunction "1_1") (pintype "passive"))
      (node (ref "X9") (pin "2") (pinfunction "S_2") (pintype "passive"))
    )
    (net (code "64") (name "Net-(X9C-S)") (class "Default")
      (node (ref "R51") (pin "2") (pinfunction "2_2") (pintype "passive"))
      (node (ref "X9") (pin "3") (pinfunction "S_3") (pintype "passive"))
    )
    (net (code "65") (name "Net-(X10B-S)") (class "Default")
      (node (ref "R53") (pin "1") (pinfunction "1_1") (pintype "passive"))
      (node (ref "X10") (pin "2") (pinfunction "S_2") (pintype "passive"))
    )
    (net (code "66") (name "Net-(X10C-S)") (class "Default")
      (node (ref "X10") (pin "3") (pinfunction "S_3") (pintype "passive"))
      (node (ref "X4") (pin "2") (pinfunction "KL_2") (pintype "passive"))
    )
    (net (code "67") (name "Net-(X11A-KL)") (class "Default")
      (node (ref "R60") (pin "2") (pinfunction "2_2") (pintype "passive"))
      (node (ref "R61") (pin "2") (pinfunction "2_2") (pintype "passive"))
      (node (ref "X11") (pin "1") (pinfunction "KL_1") (pintype "passive"))
    )
    (net (code "68") (name "Net-(X11B-KL)") (class "Default")
      (node (ref "R50") (pin "1") (pinfunction "1_1") (pintype "passive"))
      (node (ref "X11") (pin "2") (pinfunction "KL_2") (pintype "passive"))
    )
    (net (code "69") (name "Net-(X14B-S)") (class "Default")
      (node (ref "R64") (pin "1") (pinfunction "1_1") (pintype "passive"))
      (node (ref "X14") (pin "2") (pinfunction "S_2") (pintype "passive"))
      (node (ref "X14") (pin "3") (pinfunction "S_3") (pintype "passive"))
    )
    (net (code "70") (name "Net-(X15B-S)") (class "Default")
      (node (ref "R65") (pin "1") (pinfunction "1_1") (pintype "passive"))
      (node (ref "X15") (pin "2") (pinfunction "S_2") (pintype "passive"))
    )
    (net (code "71") (name "VCC") (class "Default")
      (node (ref "C13") (pin "+") (pinfunction "+_+") (pintype "passive"))
      (node (ref "C15") (pin "+") (pinfunction "+_+") (pintype "passive"))
      (node (ref "C17") (pin "+") (pinfunction "+_+") (pintype "passive"))
      (node (ref "C19") (pin "+") (pinfunction "+_+") (pintype "passive"))
      (node (ref "C4") (pin "2") (pinfunction "2_2") (pintype "passive"))
      (node (ref "IC1") (pin "4") (pinfunction "V+_4") (pintype "power_in"))
      (node (ref "IC2") (pin "8") (pinfunction "V+_8") (pintype "power_in"))
      (node (ref "IC3") (pin "8") (pinfunction "V+_8") (pintype "power_in"))
      (node (ref "IC4") (pin "8") (pinfunction "V+_8") (pintype "power_in"))
      (node (ref "IC5") (pin "8") (pinfunction "V+_8") (pintype "power_in"))
      (node (ref "R11") (pin "2") (pinfunction "2_2") (pintype "passive"))
      (node (ref "R13") (pin "1") (pinfunction "1_1") (pintype "passive"))
      (node (ref "R23") (pin "2") (pinfunction "2_2") (pintype "passive"))
      (node (ref "R38") (pin "2") (pinfunction "2_2") (pintype "passive"))
      (node (ref "R41") (pin "2") (pinfunction "2_2") (pintype "passive"))
      (node (ref "R42") (pin "2") (pinfunction "2_2") (pintype "passive"))
      (node (ref "R51") (pin "1") (pinfunction "1_1") (pintype "passive"))
      (node (ref "X1") (pin "3") (pinfunction "S_3") (pintype "passive"))
      (node (ref "X13") (pin "1") (pinfunction "KL_1") (pintype "passive"))
      (node (ref "X15") (pin "3") (pinfunction "S_3") (pintype "passive"))
      (node (ref "X2") (pin "3") (pinfunction "S_3") (pintype "passive"))
    )
    (net (code "72") (name "VEE") (class "Default")
      (node (ref "C14") (pin "-") (pinfunction "-_-") (pintype "passive"))
      (node (ref "C16") (pin "-") (pinfunction "-_-") (pintype "passive"))
      (node (ref "C18") (pin "-") (pinfunction "-_-") (pintype "passive"))
      (node (ref "C20") (pin "-") (pinfunction "-_-") (pintype "passive"))
      (node (ref "C8") (pin "2") (pinfunction "2_2") (pintype "passive"))
      (node (ref "IC1") (pin "11") (pinfunction "V-_11") (pintype "power_in"))
      (node (ref "IC2") (pin "4") (pinfunction "V-_4") (pintype "power_in"))
      (node (ref "IC3") (pin "4") (pinfunction "V-_4") (pintype "power_in"))
      (node (ref "IC4") (pin "4") (pinfunction "V-_4") (pintype "power_in"))
      (node (ref "IC5") (pin "4") (pinfunction "V-_4") (pintype "power_in"))
      (node (ref "R18") (pin "1") (pinfunction "1_1") (pintype "passive"))
      (node (ref "R36") (pin "1") (pinfunction "1_1") (pintype "passive"))
      (node (ref "R49") (pin "1") (pinfunction "1_1") (pintype "passive"))
      (node (ref "R52") (pin "2") (pinfunction "2_2") (pintype "passive"))
      (node (ref "X1") (pin "1") (pinfunction "S_1") (pintype "passive"))
      (node (ref "X13") (pin "3") (pinfunction "KL_3") (pintype "passive"))
      (node (ref "X15") (pin "1") (pinfunction "S_1") (pintype "passive"))
      (node (ref "X2") (pin "1") (pinfunction "S_1") (pintype "passive"))
    )
    (net (code "73") (name "unconnected-(IC5B-OUT-Pad7)") (class "Default")
      (node (ref "IC5") (pin "7") (pinfunction "OUT_7") (pintype "output"))
    )
  )
)
